# FZ-FILTER.net
KiCad netlist of a schematic drawn in EAGLE
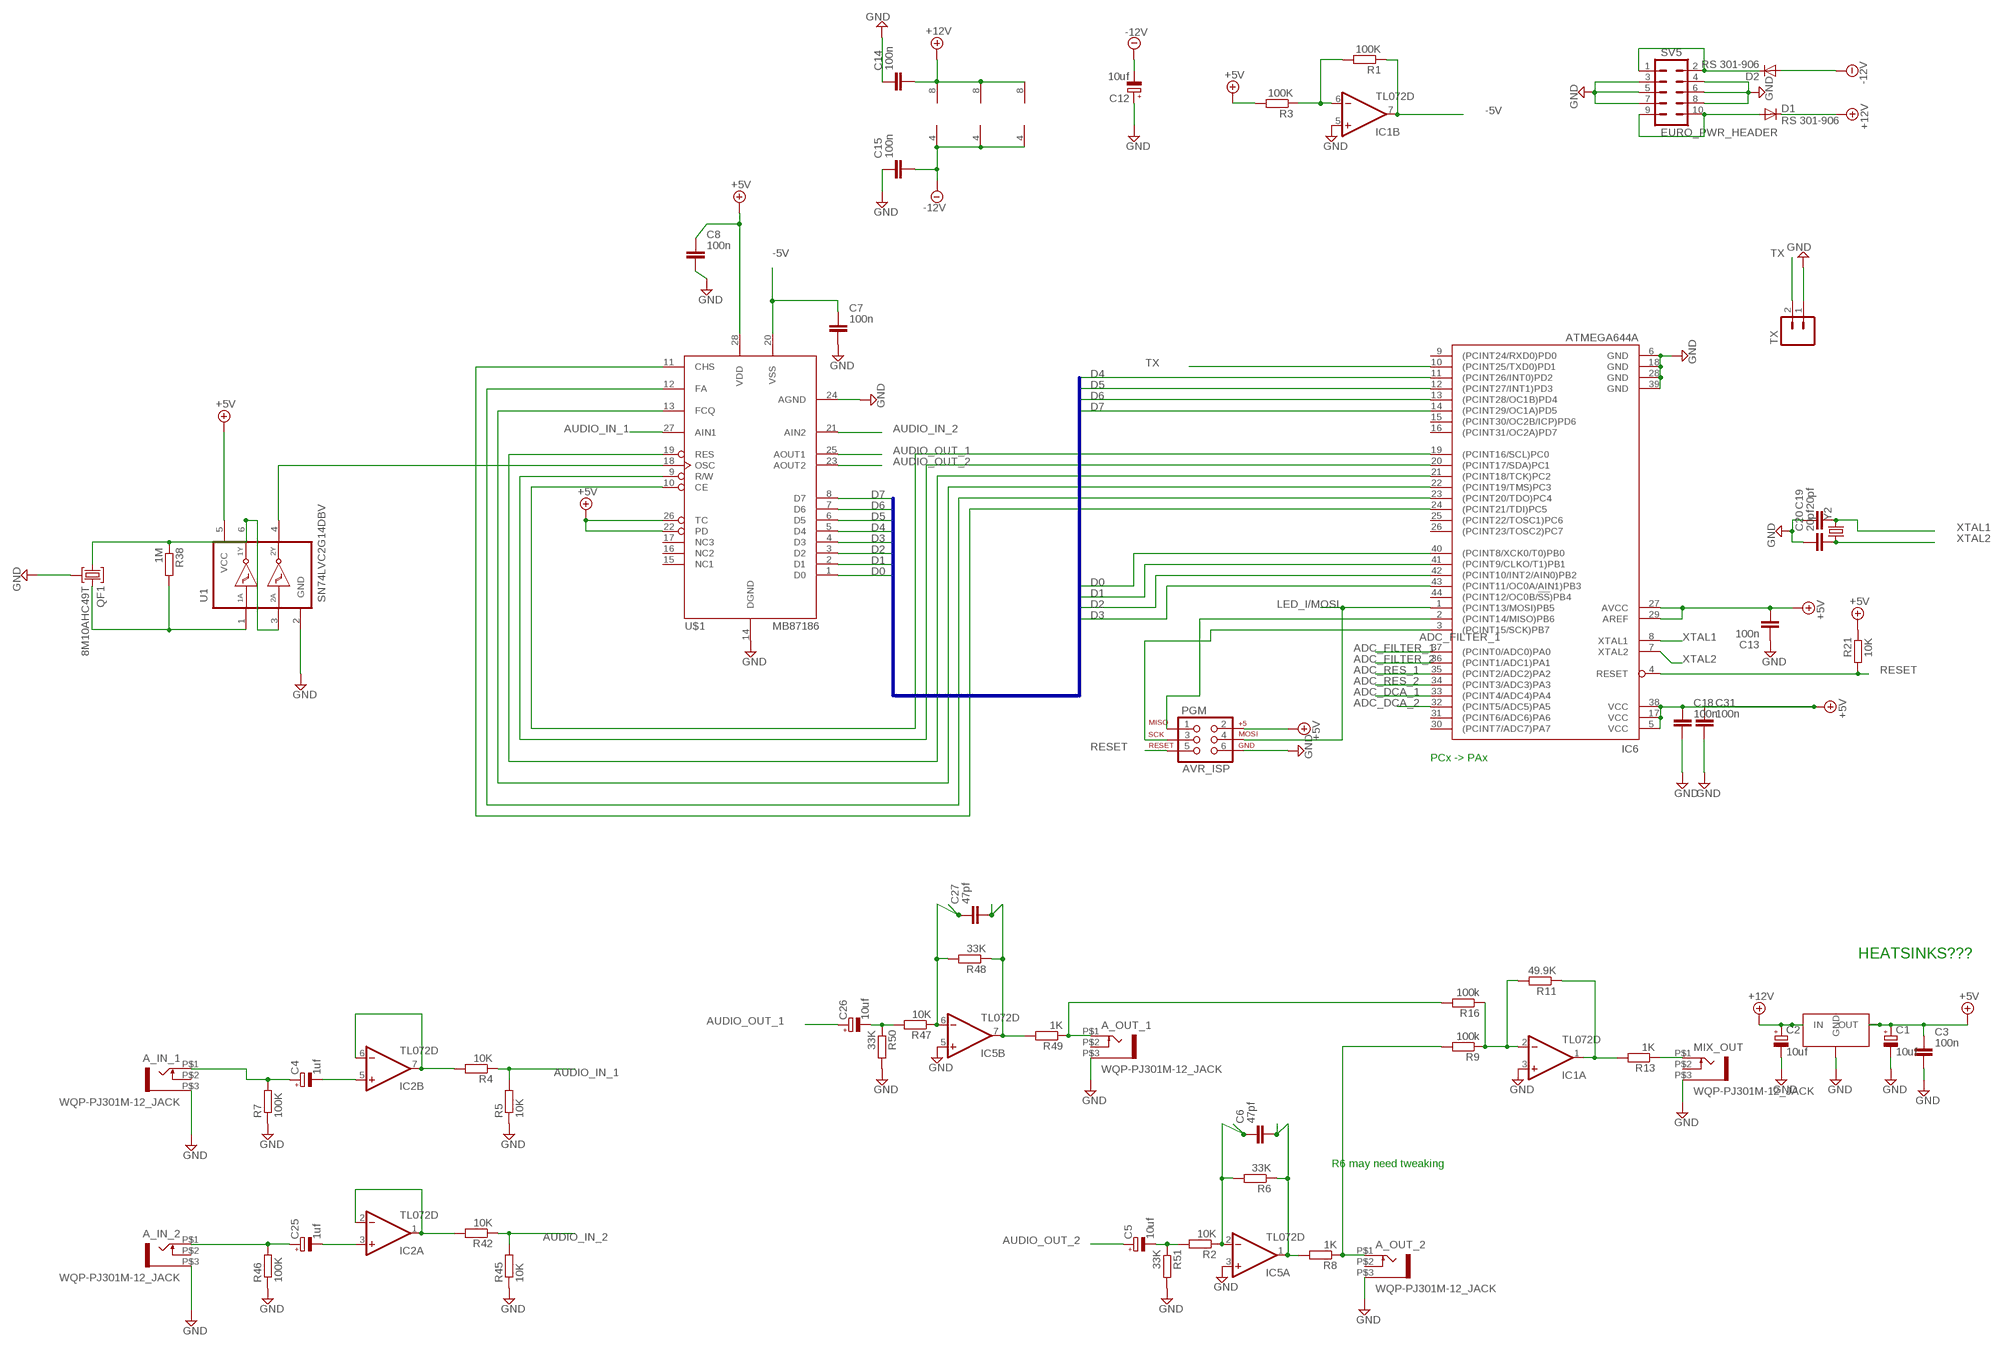
[diagram p0: schematic, sheet 1]
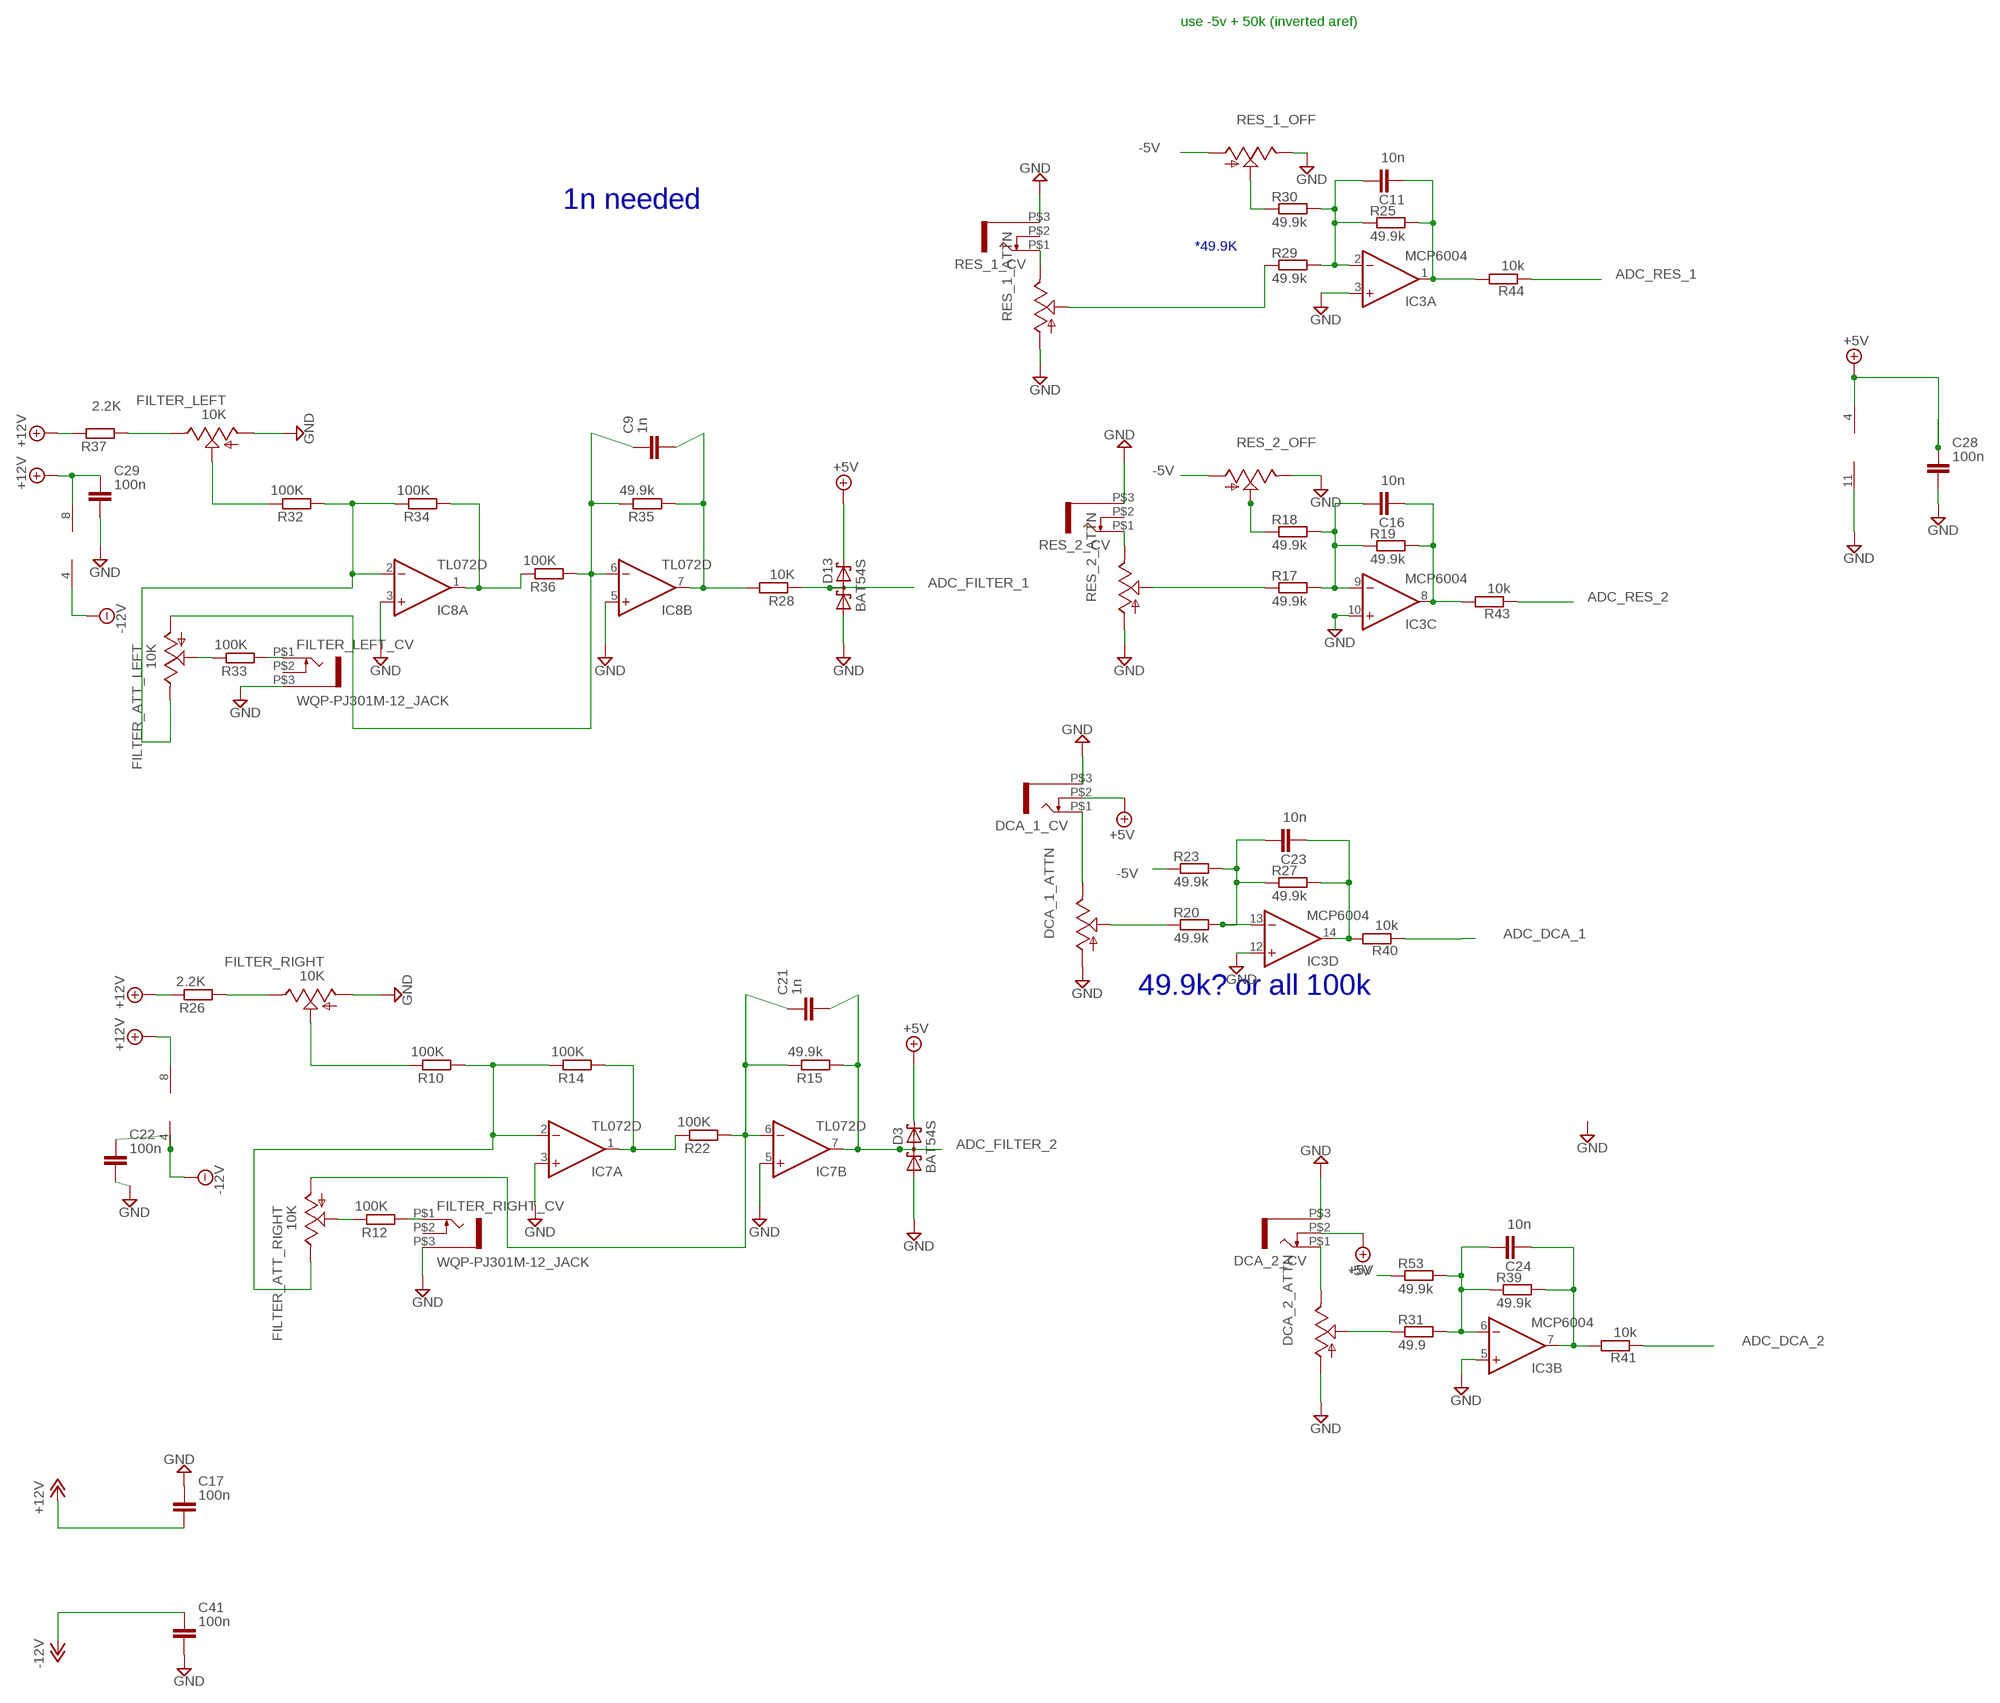
[diagram p1: schematic, sheet 2]

(export (version "E")
  (design (tool "Eeschema 10.0.6"))
  (components
    (comp (ref "C9")
      (value "1n")
      (footprint "eagle-import:C0603")
      (libsource (lib "eagle-import") (part "CAPACITOR0603"))
    )
    (comp (ref "C11")
      (value "10n")
      (footprint "eagle-import:C0603")
      (libsource (lib "eagle-import") (part "local_CAPACITOR0603"))
    )
    (comp (ref "C16")
      (value "10n")
      (footprint "eagle-import:C0603")
      (libsource (lib "eagle-import") (part "local_CAPACITOR0603"))
    )
    (comp (ref "C17")
      (value "100n")
      (footprint "eagle-import:C0603")
      (libsource (lib "eagle-import") (part "CAPACITOR0603"))
    )
    (comp (ref "C21")
      (value "1n")
      (footprint "eagle-import:C0603")
      (libsource (lib "eagle-import") (part "CAPACITOR0603"))
    )
    (comp (ref "C22")
      (value "100n")
      (footprint "eagle-import:C0603")
      (libsource (lib "eagle-import") (part "CAPACITOR0603"))
    )
    (comp (ref "C23")
      (value "10n")
      (footprint "eagle-import:C0603")
      (libsource (lib "eagle-import") (part "local_CAPACITOR0603"))
    )
    (comp (ref "C24")
      (value "10n")
      (footprint "eagle-import:C0603")
      (libsource (lib "eagle-import") (part "local_CAPACITOR0603"))
    )
    (comp (ref "C28")
      (value "100n")
      (footprint "eagle-import:C0603")
      (libsource (lib "eagle-import") (part "CAPACITOR0603"))
    )
    (comp (ref "C29")
      (value "100n")
      (footprint "eagle-import:C0603")
      (libsource (lib "eagle-import") (part "CAPACITOR0603"))
    )
    (comp (ref "C41")
      (value "100n")
      (footprint "eagle-import:C0603")
      (libsource (lib "eagle-import") (part "CAPACITOR0603"))
    )
    (comp (ref "D3")
      (value "BAT54S")
      (footprint "eagle-import:SOT23")
      (libsource (lib "eagle-import") (part "BAT54S"))
    )
    (comp (ref "D13")
      (value "BAT54S")
      (footprint "eagle-import:SOT23")
      (libsource (lib "eagle-import") (part "BAT54S"))
    )
    (comp (ref "DCA_1_ATTN")
      (value "ALPHA-9MMA")
      (footprint "eagle-import:EVUF")
      (libsource (lib "eagle-import") (part "ALPHA-9MMA"))
    )
    (comp (ref "DCA_1_CV")
      (value "WQP-PJ301M-12_JACK")
      (footprint "eagle-import:WQP-PJ301M-12_JACK")
      (libsource (lib "eagle-import") (part "WQP-PJ301M-12_JACK"))
    )
    (comp (ref "DCA_2_ATTN")
      (value "ALPHA-9MMA")
      (footprint "eagle-import:EVUF")
      (libsource (lib "eagle-import") (part "ALPHA-9MMA"))
    )
    (comp (ref "DCA_2_CV")
      (value "WQP-PJ301M-12_JACK")
      (footprint "eagle-import:WQP-PJ301M-12_JACK")
      (libsource (lib "eagle-import") (part "WQP-PJ301M-12_JACK"))
    )
    (comp (ref "FILTER_ATT_LEFT")
      (value "10K")
      (footprint "eagle-import:EVUF")
      (libsource (lib "eagle-import") (part "ALPHA-9MMA"))
    )
    (comp (ref "FILTER_ATT_RIGHT")
      (value "10K")
      (footprint "eagle-import:EVUF")
      (libsource (lib "eagle-import") (part "ALPHA-9MMA"))
    )
    (comp (ref "FILTER_LEFT")
      (value "10K")
      (footprint "eagle-import:EVUF")
      (libsource (lib "eagle-import") (part "ALPHA-9MMA"))
    )
    (comp (ref "FILTER_LEFT_CV")
      (value "WQP-PJ301M-12_JACK")
      (footprint "eagle-import:WQP-PJ301M-12_JACK")
      (libsource (lib "eagle-import") (part "WQP-PJ301M-12_JACK"))
    )
    (comp (ref "FILTER_RIGHT")
      (value "10K")
      (footprint "eagle-import:EVUF")
      (libsource (lib "eagle-import") (part "ALPHA-9MMA"))
    )
    (comp (ref "FILTER_RIGHT_CV")
      (value "WQP-PJ301M-12_JACK")
      (footprint "eagle-import:WQP-PJ301M-12_JACK")
      (libsource (lib "eagle-import") (part "WQP-PJ301M-12_JACK"))
    )
    (comp (ref "IC3")
      (value "MCP6004")
      (footprint "eagle-import:SO14")
      (libsource (lib "eagle-import") (part "TL074D"))
    )
    (comp (ref "IC7")
      (value "TL072D")
      (footprint "eagle-import:SO08")
      (libsource (lib "eagle-import") (part "TL072D"))
    )
    (comp (ref "IC8")
      (value "TL072D")
      (footprint "eagle-import:SO08")
      (libsource (lib "eagle-import") (part "TL072D"))
    )
    (comp (ref "R10")
      (value "100K")
      (footprint "eagle-import:R0603")
      (libsource (lib "eagle-import") (part "RESISTOR0603"))
    )
    (comp (ref "R12")
      (value "100K")
      (footprint "eagle-import:R0603")
      (libsource (lib "eagle-import") (part "RESISTOR0603"))
    )
    (comp (ref "R14")
      (value "100K")
      (footprint "eagle-import:R0603")
      (libsource (lib "eagle-import") (part "RESISTOR0603"))
    )
    (comp (ref "R15")
      (value "49.9k")
      (footprint "eagle-import:R0603")
      (libsource (lib "eagle-import") (part "RESISTOR0603"))
    )
    (comp (ref "R17")
      (value "49.9k")
      (footprint "eagle-import:R0603")
      (libsource (lib "eagle-import") (part "RESISTOR0603"))
    )
    (comp (ref "R18")
      (value "49.9k")
      (footprint "eagle-import:R0603")
      (libsource (lib "eagle-import") (part "RESISTOR0603"))
    )
    (comp (ref "R19")
      (value "49.9k")
      (footprint "eagle-import:R0603")
      (libsource (lib "eagle-import") (part "RESISTOR0603"))
    )
    (comp (ref "R20")
      (value "49.9k")
      (footprint "eagle-import:R0603")
      (libsource (lib "eagle-import") (part "RESISTOR0603"))
    )
    (comp (ref "R22")
      (value "100K")
      (footprint "eagle-import:R0603")
      (libsource (lib "eagle-import") (part "RESISTOR0603"))
    )
    (comp (ref "R23")
      (value "49.9k")
      (footprint "eagle-import:R0603")
      (libsource (lib "eagle-import") (part "RESISTOR0603"))
    )
    (comp (ref "R25")
      (value "49.9k")
      (footprint "eagle-import:R0603")
      (libsource (lib "eagle-import") (part "RESISTOR0603"))
    )
    (comp (ref "R26")
      (value "2.2K")
      (footprint "eagle-import:R0603")
      (libsource (lib "eagle-import") (part "RESISTOR0603"))
    )
    (comp (ref "R27")
      (value "49.9k")
      (footprint "eagle-import:R0603")
      (libsource (lib "eagle-import") (part "RESISTOR0603"))
    )
    (comp (ref "R28")
      (value "10K")
      (footprint "eagle-import:R0603")
      (libsource (lib "eagle-import") (part "RESISTOR0603"))
    )
    (comp (ref "R29")
      (value "49.9k")
      (footprint "eagle-import:R0603")
      (libsource (lib "eagle-import") (part "RESISTOR0603"))
    )
    (comp (ref "R30")
      (value "49.9k")
      (footprint "eagle-import:R0603")
      (libsource (lib "eagle-import") (part "RESISTOR0603"))
    )
    (comp (ref "R31")
      (value "49.9")
      (footprint "eagle-import:R0603")
      (libsource (lib "eagle-import") (part "RESISTOR0603"))
    )
    (comp (ref "R32")
      (value "100K")
      (footprint "eagle-import:R0603")
      (libsource (lib "eagle-import") (part "RESISTOR0603"))
    )
    (comp (ref "R33")
      (value "100K")
      (footprint "eagle-import:R0603")
      (libsource (lib "eagle-import") (part "RESISTOR0603"))
    )
    (comp (ref "R34")
      (value "100K")
      (footprint "eagle-import:R0603")
      (libsource (lib "eagle-import") (part "RESISTOR0603"))
    )
    (comp (ref "R35")
      (value "49.9k")
      (footprint "eagle-import:R0603")
      (libsource (lib "eagle-import") (part "RESISTOR0603"))
    )
    (comp (ref "R36")
      (value "100K")
      (footprint "eagle-import:R0603")
      (libsource (lib "eagle-import") (part "RESISTOR0603"))
    )
    (comp (ref "R37")
      (value "2.2K")
      (footprint "eagle-import:R0603")
      (libsource (lib "eagle-import") (part "RESISTOR0603"))
    )
    (comp (ref "R39")
      (value "49.9k")
      (footprint "eagle-import:R0603")
      (libsource (lib "eagle-import") (part "RESISTOR0603"))
    )
    (comp (ref "R40")
      (value "10k")
      (footprint "eagle-import:R0603")
      (libsource (lib "eagle-import") (part "RESISTOR0603"))
    )
    (comp (ref "R41")
      (value "10k")
      (footprint "eagle-import:R0603")
      (libsource (lib "eagle-import") (part "RESISTOR0603"))
    )
    (comp (ref "R43")
      (value "10k")
      (footprint "eagle-import:R0603")
      (libsource (lib "eagle-import") (part "RESISTOR0603"))
    )
    (comp (ref "R44")
      (value "10k")
      (footprint "eagle-import:R0603")
      (libsource (lib "eagle-import") (part "RESISTOR0603"))
    )
    (comp (ref "R53")
      (value "49.9k")
      (footprint "eagle-import:R0603")
      (libsource (lib "eagle-import") (part "RESISTOR0603"))
    )
    (comp (ref "RES_1_ATTN")
      (value "ALPHA-9MMA")
      (footprint "eagle-import:EVUF")
      (libsource (lib "eagle-import") (part "ALPHA-9MMA"))
    )
    (comp (ref "RES_1_CV")
      (value "WQP-PJ301M-12_JACK")
      (footprint "eagle-import:WQP-PJ301M-12_JACK")
      (libsource (lib "eagle-import") (part "WQP-PJ301M-12_JACK"))
    )
    (comp (ref "RES_1_OFF")
      (value "ALPHA-9MMA")
      (footprint "eagle-import:EVUF")
      (libsource (lib "eagle-import") (part "ALPHA-9MMA"))
    )
    (comp (ref "RES_2_ATTN")
      (value "ALPHA-9MMA")
      (footprint "eagle-import:EVUF")
      (libsource (lib "eagle-import") (part "ALPHA-9MMA"))
    )
    (comp (ref "RES_2_CV")
      (value "WQP-PJ301M-12_JACK")
      (footprint "eagle-import:WQP-PJ301M-12_JACK")
      (libsource (lib "eagle-import") (part "WQP-PJ301M-12_JACK"))
    )
    (comp (ref "RES_2_OFF")
      (value "ALPHA-9MMA")
      (footprint "eagle-import:EVUF")
      (libsource (lib "eagle-import") (part "ALPHA-9MMA"))
    )
    (comp (ref "A_IN_1")
      (value "WQP-PJ301M-12_JACK")
      (footprint "eagle-import:WQP-PJ301M-12_JACK")
      (libsource (lib "eagle-import") (part "WQP-PJ301M-12_JACK"))
    )
    (comp (ref "A_IN_2")
      (value "WQP-PJ301M-12_JACK")
      (footprint "eagle-import:WQP-PJ301M-12_JACK")
      (libsource (lib "eagle-import") (part "WQP-PJ301M-12_JACK"))
    )
    (comp (ref "A_OUT_1")
      (value "WQP-PJ301M-12_JACK")
      (footprint "eagle-import:WQP-PJ301M-12_JACK")
      (libsource (lib "eagle-import") (part "WQP-PJ301M-12_JACK"))
    )
    (comp (ref "A_OUT_2")
      (value "WQP-PJ301M-12_JACK")
      (footprint "eagle-import:WQP-PJ301M-12_JACK")
      (libsource (lib "eagle-import") (part "WQP-PJ301M-12_JACK"))
    )
    (comp (ref "C1")
      (value "10uf")
      (footprint "eagle-import:PANASONIC_B")
      (libsource (lib "eagle-import") (part "CPOL-EUB"))
    )
    (comp (ref "C2")
      (value "10uf")
      (footprint "eagle-import:PANASONIC_B")
      (libsource (lib "eagle-import") (part "CPOL-EUB"))
    )
    (comp (ref "C3")
      (value "100n")
      (footprint "eagle-import:C0603")
      (libsource (lib "eagle-import") (part "CAPACITOR0603"))
    )
    (comp (ref "C4")
      (value "1uf")
      (footprint "eagle-import:PANASONIC_B")
      (libsource (lib "eagle-import") (part "CPOL-EUB"))
    )
    (comp (ref "C5")
      (value "10uf")
      (footprint "eagle-import:PANASONIC_B")
      (libsource (lib "eagle-import") (part "CPOL-EUB"))
    )
    (comp (ref "C6")
      (value "47pf")
      (footprint "eagle-import:C0603")
      (libsource (lib "eagle-import") (part "CAPACITOR0603"))
    )
    (comp (ref "C7")
      (value "100n")
      (footprint "eagle-import:C0603")
      (libsource (lib "eagle-import") (part "CAPACITOR0603"))
    )
    (comp (ref "C8")
      (value "100n")
      (footprint "eagle-import:C0603")
      (libsource (lib "eagle-import") (part "CAPACITOR0603"))
    )
    (comp (ref "C12")
      (value "10uf")
      (footprint "eagle-import:PANASONIC_B")
      (libsource (lib "eagle-import") (part "CPOL-EUB"))
    )
    (comp (ref "C13")
      (value "100n")
      (footprint "eagle-import:C0603")
      (libsource (lib "eagle-import") (part "CAPACITOR0603"))
    )
    (comp (ref "C14")
      (value "100n")
      (footprint "eagle-import:C0603")
      (libsource (lib "eagle-import") (part "CAPACITOR0603"))
    )
    (comp (ref "C15")
      (value "100n")
      (footprint "eagle-import:C0603")
      (libsource (lib "eagle-import") (part "CAPACITOR0603"))
    )
    (comp (ref "C18")
      (value "100n")
      (footprint "eagle-import:C0603")
      (libsource (lib "eagle-import") (part "CAPACITOR0603"))
    )
    (comp (ref "C19")
      (value "20pf")
      (footprint "eagle-import:C0603")
      (libsource (lib "eagle-import") (part "CAPACITOR0603"))
    )
    (comp (ref "C20")
      (value "20pf")
      (footprint "eagle-import:C0603")
      (libsource (lib "eagle-import") (part "CAPACITOR0603"))
    )
    (comp (ref "C25")
      (value "1uf")
      (footprint "eagle-import:PANASONIC_B")
      (libsource (lib "eagle-import") (part "CPOL-EUB"))
    )
    (comp (ref "C26")
      (value "10uf")
      (footprint "eagle-import:PANASONIC_B")
      (libsource (lib "eagle-import") (part "CPOL-EUB"))
    )
    (comp (ref "C27")
      (value "47pf")
      (footprint "eagle-import:C0603")
      (libsource (lib "eagle-import") (part "CAPACITOR0603"))
    )
    (comp (ref "C31")
      (value "100n")
      (footprint "eagle-import:C0603")
      (libsource (lib "eagle-import") (part "CAPACITOR0603"))
    )
    (comp (ref "D1")
      (value "RS 301-906")
      (footprint "eagle-import:SMB-DIODE")
      (libsource (lib "eagle-import") (part "DIODESMB"))
    )
    (comp (ref "D2")
      (value "RS 301-906")
      (footprint "eagle-import:SMB-DIODE")
      (libsource (lib "eagle-import") (part "DIODESMB"))
    )
    (comp (ref "IC1")
      (value "TL072D")
      (footprint "eagle-import:SO08")
      (libsource (lib "eagle-import") (part "TL072D"))
    )
    (comp (ref "IC2")
      (value "TL072D")
      (footprint "eagle-import:SO08")
      (libsource (lib "eagle-import") (part "TL072D"))
    )
    (comp (ref "IC5")
      (value "TL072D")
      (footprint "eagle-import:SO08")
      (libsource (lib "eagle-import") (part "TL072D"))
    )
    (comp (ref "IC6")
      (value "ATMEGA644A")
      (footprint "eagle-import:TQFP44")
      (fields (field (name "MPN") "ATMEGA644PV-10AU"))
      (libsource (lib "eagle-import") (part "ATMEGA644A"))
    )
    (comp (ref "MIX_OUT")
      (value "WQP-PJ301M-12_JACK")
      (footprint "eagle-import:WQP-PJ301M-12_JACK")
      (libsource (lib "eagle-import") (part "WQP-PJ301M-12_JACK"))
    )
    (comp (ref "PGM")
      (value "AVR_ISP")
      (footprint "eagle-import:2X3")
      (libsource (lib "eagle-import") (part "AVR_SPI_PRG_6PTH"))
    )
    (comp (ref "QF1")
      (value "8M10AHC49T")
      (footprint "eagle-import:HC49U")
      (libsource (lib "eagle-import") (part "8M10AHC49T"))
    )
    (comp (ref "R1")
      (value "100K")
      (footprint "eagle-import:R0603")
      (libsource (lib "eagle-import") (part "RESISTOR0603"))
    )
    (comp (ref "R2")
      (value "10K")
      (footprint "eagle-import:R0603")
      (libsource (lib "eagle-import") (part "RESISTOR0603"))
    )
    (comp (ref "R3")
      (value "100K")
      (footprint "eagle-import:R0603")
      (libsource (lib "eagle-import") (part "RESISTOR0603"))
    )
    (comp (ref "R4")
      (value "10K")
      (footprint "eagle-import:R0603")
      (libsource (lib "eagle-import") (part "RESISTOR0603"))
    )
    (comp (ref "R5")
      (value "10K")
      (footprint "eagle-import:R0603")
      (libsource (lib "eagle-import") (part "RESISTOR0603"))
    )
    (comp (ref "R6")
      (value "33K")
      (footprint "eagle-import:R0603")
      (libsource (lib "eagle-import") (part "RESISTOR0603"))
    )
    (comp (ref "R7")
      (value "100K")
      (footprint "eagle-import:R0603")
      (libsource (lib "eagle-import") (part "RESISTOR0603"))
    )
    (comp (ref "R8")
      (value "1K")
      (footprint "eagle-import:R0603")
      (libsource (lib "eagle-import") (part "RESISTOR0603"))
    )
    (comp (ref "R9")
      (value "100k")
      (footprint "eagle-import:R0603")
      (libsource (lib "eagle-import") (part "RESISTOR0603"))
    )
    (comp (ref "R11")
      (value "49.9K")
      (footprint "eagle-import:R0603")
      (libsource (lib "eagle-import") (part "RESISTOR0603"))
    )
    (comp (ref "R13")
      (value "1K")
      (footprint "eagle-import:R0603")
      (libsource (lib "eagle-import") (part "RESISTOR0603"))
    )
    (comp (ref "R16")
      (value "100k")
      (footprint "eagle-import:R0603")
      (libsource (lib "eagle-import") (part "RESISTOR0603"))
    )
    (comp (ref "R21")
      (value "10K")
      (footprint "eagle-import:R0603")
      (libsource (lib "eagle-import") (part "RESISTOR0603"))
    )
    (comp (ref "R38")
      (value "1M")
      (footprint "eagle-import:R0603")
      (libsource (lib "eagle-import") (part "RESISTOR0603"))
    )
    (comp (ref "R42")
      (value "10K")
      (footprint "eagle-import:R0603")
      (libsource (lib "eagle-import") (part "RESISTOR0603"))
    )
    (comp (ref "R45")
      (value "10K")
      (footprint "eagle-import:R0603")
      (libsource (lib "eagle-import") (part "RESISTOR0603"))
    )
    (comp (ref "R46")
      (value "100K")
      (footprint "eagle-import:R0603")
      (libsource (lib "eagle-import") (part "RESISTOR0603"))
    )
    (comp (ref "R47")
      (value "10K")
      (footprint "eagle-import:R0603")
      (libsource (lib "eagle-import") (part "RESISTOR0603"))
    )
    (comp (ref "R48")
      (value "33K")
      (footprint "eagle-import:R0603")
      (libsource (lib "eagle-import") (part "RESISTOR0603"))
    )
    (comp (ref "R49")
      (value "1K")
      (footprint "eagle-import:R0603")
      (libsource (lib "eagle-import") (part "RESISTOR0603"))
    )
    (comp (ref "R50")
      (value "33K")
      (footprint "eagle-import:R0603")
      (libsource (lib "eagle-import") (part "RESISTOR0603"))
    )
    (comp (ref "R51")
      (value "33K")
      (footprint "eagle-import:R0603")
      (libsource (lib "eagle-import") (part "RESISTOR0603"))
    )
    (comp (ref "SV5")
      (value "EURO_PWR_HEADER")
      (footprint "eagle-import:EURO_PWR_HEADER")
      (libsource (lib "eagle-import") (part "EURO_PWR_HEADER"))
    )
    (comp (ref "TX")
      (value "M02PTH")
      (footprint "eagle-import:1X02")
      (libsource (lib "eagle-import") (part "M02PTH"))
    )
    (comp (ref "U$1")
      (value "MB87186")
      (footprint "eagle-import:DIP28")
      (libsource (lib "eagle-import") (part "MB87186"))
    )
    (comp (ref "U1")
      (value "SN74LVC2G14DBV")
      (footprint "eagle-import:SOT23-6")
      (libsource (lib "eagle-import") (part "SN74LVC2G14DBV"))
    )
    (comp (ref "U3")
      (value "7805")
      (footprint "eagle-import:VREG-7805-DPAK2")
      (libsource (lib "eagle-import") (part "VREG-7805-DPAK2"))
    )
    (comp (ref "Y2")
      (value "CRYSTALSMD")
      (footprint "eagle-import:HC49UP")
      (libsource (lib "eagle-import") (part "CRYSTALSMD"))
    )
  )
  (nets
    (net (code "1") (name "+5V") (class "Default")
      (node (ref "C1") (pin "+") (pinfunction "+_+") (pintype "passive"))
      (node (ref "C13") (pin "2") (pinfunction "2_2") (pintype "passive"))
      (node (ref "C18") (pin "1") (pinfunction "1_1") (pintype "passive"))
      (node (ref "C28") (pin "1") (pinfunction "1_1") (pintype "passive"))
      (node (ref "C3") (pin "1") (pinfunction "1_1") (pintype "passive"))
      (node (ref "C31") (pin "1") (pinfunction "1_1") (pintype "passive"))
      (node (ref "C8") (pin "1") (pinfunction "1_1") (pintype "passive"))
      (node (ref "D13") (pin "2") (pinfunction "C2_2") (pintype "passive"))
      (node (ref "D3") (pin "2") (pinfunction "C2_2") (pintype "passive"))
      (node (ref "DCA_1_CV") (pin "P$2") (pinfunction "3_P$2") (pintype "passive"))
      (node (ref "DCA_2_CV") (pin "P$2") (pinfunction "3_P$2") (pintype "passive"))
      (node (ref "IC3") (pin "4") (pinfunction "V+_4") (pintype "power_in"))
      (node (ref "IC6") (pin "17") (pinfunction "VCC_17") (pintype "power_in"))
      (node (ref "IC6") (pin "27") (pinfunction "AVCC_27") (pintype "power_in"))
      (node (ref "IC6") (pin "29") (pinfunction "AREF_29") (pintype "passive"))
      (node (ref "IC6") (pin "38") (pinfunction "VCC_38") (pintype "power_in"))
      (node (ref "IC6") (pin "5") (pinfunction "VCC_5") (pintype "power_in"))
      (node (ref "PGM") (pin "2") (pinfunction "2_2") (pintype "passive"))
      (node (ref "R21") (pin "2") (pinfunction "2_2") (pintype "passive"))
      (node (ref "R3") (pin "2") (pinfunction "2_2") (pintype "passive"))
      (node (ref "U$1") (pin "22") (pinfunction "PD_22") (pintype "input"))
      (node (ref "U$1") (pin "26") (pinfunction "TC_26") (pintype "input"))
      (node (ref "U$1") (pin "28") (pinfunction "VDD_28") (pintype "power_in"))
      (node (ref "U1") (pin "5") (pinfunction "VCC_5") (pintype "power_in"))
      (node (ref "U3") (pin "VOUT") (pinfunction "OUT_VOUT") (pintype "bidirectional"))
    )
    (net (code "2") (name "+12V") (class "Default")
      (node (ref "C14") (pin "2") (pinfunction "2_2") (pintype "passive"))
      (node (ref "C17") (pin "2") (pinfunction "2_2") (pintype "passive"))
      (node (ref "C2") (pin "+") (pinfunction "+_+") (pintype "passive"))
      (node (ref "C29") (pin "1") (pinfunction "1_1") (pintype "passive"))
      (node (ref "D1") (pin "C") (pinfunction "C_C") (pintype "passive"))
      (node (ref "IC1") (pin "8") (pinfunction "V+_8") (pintype "power_in"))
      (node (ref "IC2") (pin "8") (pinfunction "V+_8") (pintype "power_in"))
      (node (ref "IC5") (pin "8") (pinfunction "V+_8") (pintype "power_in"))
      (node (ref "IC7") (pin "8") (pinfunction "V+_8") (pintype "power_in"))
      (node (ref "IC8") (pin "8") (pinfunction "V+_8") (pintype "power_in"))
      (node (ref "R26") (pin "2") (pinfunction "2_2") (pintype "passive"))
      (node (ref "R37") (pin "2") (pinfunction "2_2") (pintype "passive"))
      (node (ref "U3") (pin "VIN") (pinfunction "IN_VIN") (pintype "bidirectional"))
    )
    (net (code "3") (name "-5V") (class "Default")
      (node (ref "C7") (pin "1") (pinfunction "1_1") (pintype "passive"))
      (node (ref "IC1") (pin "7") (pinfunction "OUT_7") (pintype "output"))
      (node (ref "R1") (pin "1") (pinfunction "1_1") (pintype "passive"))
      (node (ref "R23") (pin "1") (pinfunction "1_1") (pintype "passive"))
      (node (ref "R53") (pin "1") (pinfunction "1_1") (pintype "passive"))
      (node (ref "RES_1_OFF") (pin "1") (pinfunction "A_1") (pintype "passive"))
      (node (ref "RES_2_OFF") (pin "1") (pinfunction "A_1") (pintype "passive"))
      (node (ref "U$1") (pin "20") (pinfunction "VSS_20") (pintype "power_in"))
    )
    (net (code "4") (name "-12V") (class "Default")
      (node (ref "C12") (pin "-") (pinfunction "-_-") (pintype "passive"))
      (node (ref "C15") (pin "2") (pinfunction "2_2") (pintype "passive"))
      (node (ref "C22") (pin "1") (pinfunction "1_1") (pintype "passive"))
      (node (ref "C41") (pin "1") (pinfunction "1_1") (pintype "passive"))
      (node (ref "D2") (pin "A") (pinfunction "A_A") (pintype "passive"))
      (node (ref "IC1") (pin "4") (pinfunction "V-_4") (pintype "power_in"))
      (node (ref "IC2") (pin "4") (pinfunction "V-_4") (pintype "power_in"))
      (node (ref "IC5") (pin "4") (pinfunction "V-_4") (pintype "power_in"))
      (node (ref "IC7") (pin "4") (pinfunction "V-_4") (pintype "power_in"))
      (node (ref "IC8") (pin "4") (pinfunction "V-_4") (pintype "power_in"))
    )
    (net (code "5") (name "ADC_DCA_1") (class "Default")
      (node (ref "IC6") (pin "33") (pinfunction "(PCINT4/ADC4)PA4_33") (pintype "bidirectional"))
      (node (ref "R40") (pin "1") (pinfunction "1_1") (pintype "passive"))
    )
    (net (code "6") (name "ADC_DCA_2") (class "Default")
      (node (ref "IC6") (pin "32") (pinfunction "(PCINT5/ADC5)PA5_32") (pintype "bidirectional"))
      (node (ref "R41") (pin "1") (pinfunction "1_1") (pintype "passive"))
    )
    (net (code "7") (name "ADC_FILTER_1") (class "Default")
      (node (ref "D13") (pin "3") (pinfunction "C1A2_3") (pintype "passive"))
      (node (ref "IC6") (pin "37") (pinfunction "(PCINT0/ADC0)PA0_37") (pintype "bidirectional"))
      (node (ref "R28") (pin "1") (pinfunction "1_1") (pintype "passive"))
    )
    (net (code "8") (name "ADC_FILTER_2") (class "Default")
      (node (ref "C21") (pin "2") (pinfunction "2_2") (pintype "passive"))
      (node (ref "D3") (pin "3") (pinfunction "C1A2_3") (pintype "passive"))
      (node (ref "IC6") (pin "36") (pinfunction "(PCINT1/ADC1)PA1_36") (pintype "bidirectional"))
      (node (ref "IC7") (pin "7") (pinfunction "OUT_7") (pintype "output"))
      (node (ref "R15") (pin "1") (pinfunction "1_1") (pintype "passive"))
    )
    (net (code "9") (name "ADC_RES_1") (class "Default")
      (node (ref "IC6") (pin "35") (pinfunction "(PCINT2/ADC2)PA2_35") (pintype "bidirectional"))
      (node (ref "R44") (pin "1") (pinfunction "1_1") (pintype "passive"))
    )
    (net (code "10") (name "ADC_RES_2") (class "Default")
      (node (ref "IC6") (pin "34") (pinfunction "(PCINT3/ADC3)PA3_34") (pintype "bidirectional"))
      (node (ref "R43") (pin "1") (pinfunction "1_1") (pintype "passive"))
    )
    (net (code "11") (name "AUDIO_IN_1") (class "Default")
      (node (ref "R4") (pin "1") (pinfunction "1_1") (pintype "passive"))
      (node (ref "R5") (pin "2") (pinfunction "2_2") (pintype "passive"))
      (node (ref "U$1") (pin "27") (pinfunction "AIN1_27") (pintype "bidirectional"))
    )
    (net (code "12") (name "AUDIO_IN_2") (class "Default")
      (node (ref "R42") (pin "1") (pinfunction "1_1") (pintype "passive"))
      (node (ref "R45") (pin "2") (pinfunction "2_2") (pintype "passive"))
      (node (ref "U$1") (pin "21") (pinfunction "AIN2_21") (pintype "input"))
    )
    (net (code "13") (name "AUDIO_OUT_1") (class "Default")
      (node (ref "C26") (pin "+") (pinfunction "+_+") (pintype "passive"))
      (node (ref "U$1") (pin "25") (pinfunction "AOUT1_25") (pintype "tri_state"))
    )
    (net (code "14") (name "AUDIO_OUT_2") (class "Default")
      (node (ref "C5") (pin "+") (pinfunction "+_+") (pintype "passive"))
      (node (ref "U$1") (pin "23") (pinfunction "AOUT2_23") (pintype "tri_state"))
    )
    (net (code "15") (name "D0") (class "Default")
      (node (ref "IC6") (pin "40") (pinfunction "(PCINT8/XCK0/T0)PB0_40") (pintype "bidirectional"))
      (node (ref "U$1") (pin "1") (pinfunction "D0_1") (pintype "bidirectional"))
    )
    (net (code "16") (name "D1") (class "Default")
      (node (ref "IC6") (pin "41") (pinfunction "(PCINT9/CLKO/T1)PB1_41") (pintype "bidirectional"))
      (node (ref "U$1") (pin "2") (pinfunction "D1_2") (pintype "bidirectional"))
    )
    (net (code "17") (name "D2") (class "Default")
      (node (ref "IC6") (pin "42") (pinfunction "(PCINT10/INT2/AIN0)PB2_42") (pintype "bidirectional"))
      (node (ref "U$1") (pin "3") (pinfunction "D2_3") (pintype "bidirectional"))
    )
    (net (code "18") (name "D3") (class "Default")
      (node (ref "IC6") (pin "43") (pinfunction "(PCINT11/OC0A/AIN1)PB3_43") (pintype "bidirectional"))
      (node (ref "U$1") (pin "4") (pinfunction "D3_4") (pintype "bidirectional"))
    )
    (net (code "19") (name "D4") (class "Default")
      (node (ref "IC6") (pin "11") (pinfunction "(PCINT26/INT0)PD2_11") (pintype "bidirectional"))
      (node (ref "U$1") (pin "5") (pinfunction "D4_5") (pintype "bidirectional"))
    )
    (net (code "20") (name "D5") (class "Default")
      (node (ref "IC6") (pin "12") (pinfunction "(PCINT27/INT1)PD3_12") (pintype "bidirectional"))
      (node (ref "U$1") (pin "6") (pinfunction "D5_6") (pintype "bidirectional"))
    )
    (net (code "21") (name "D6") (class "Default")
      (node (ref "IC6") (pin "13") (pinfunction "(PCINT28/OC1B)PD4_13") (pintype "bidirectional"))
      (node (ref "U$1") (pin "7") (pinfunction "D6_7") (pintype "bidirectional"))
    )
    (net (code "22") (name "D7") (class "Default")
      (node (ref "IC6") (pin "14") (pinfunction "(PCINT29/OC1A)PD5_14") (pintype "bidirectional"))
      (node (ref "U$1") (pin "8") (pinfunction "D7_8") (pintype "bidirectional"))
    )
    (net (code "23") (name "GND") (class "Default")
      (node (ref "A_IN_1") (pin "P$3") (pinfunction "1_P$3") (pintype "passive"))
      (node (ref "A_IN_2") (pin "P$3") (pinfunction "1_P$3") (pintype "passive"))
      (node (ref "A_OUT_1") (pin "P$3") (pinfunction "1_P$3") (pintype "passive"))
      (node (ref "A_OUT_2") (pin "P$3") (pinfunction "1_P$3") (pintype "passive"))
      (node (ref "C1") (pin "-") (pinfunction "-_-") (pintype "passive"))
      (node (ref "C12") (pin "+") (pinfunction "+_+") (pintype "passive"))
      (node (ref "C13") (pin "1") (pinfunction "1_1") (pintype "passive"))
      (node (ref "C14") (pin "1") (pinfunction "1_1") (pintype "passive"))
      (node (ref "C15") (pin "1") (pinfunction "1_1") (pintype "passive"))
      (node (ref "C17") (pin "1") (pinfunction "1_1") (pintype "passive"))
      (node (ref "C18") (pin "2") (pinfunction "2_2") (pintype "passive"))
      (node (ref "C19") (pin "1") (pinfunction "1_1") (pintype "passive"))
      (node (ref "C2") (pin "-") (pinfunction "-_-") (pintype "passive"))
      (node (ref "C20") (pin "1") (pinfunction "1_1") (pintype "passive"))
      (node (ref "C22") (pin "2") (pinfunction "2_2") (pintype "passive"))
      (node (ref "C28") (pin "2") (pinfunction "2_2") (pintype "passive"))
      (node (ref "C29") (pin "2") (pinfunction "2_2") (pintype "passive"))
      (node (ref "C3") (pin "2") (pinfunction "2_2") (pintype "passive"))
      (node (ref "C31") (pin "2") (pinfunction "2_2") (pintype "passive"))
      (node (ref "C41") (pin "2") (pinfunction "2_2") (pintype "passive"))
      (node (ref "C7") (pin "2") (pinfunction "2_2") (pintype "passive"))
      (node (ref "C8") (pin "2") (pinfunction "2_2") (pintype "passive"))
      (node (ref "D13") (pin "1") (pinfunction "A1_1") (pintype "passive"))
      (node (ref "D3") (pin "1") (pinfunction "A1_1") (pintype "passive"))
      (node (ref "DCA_1_ATTN") (pin "1") (pinfunction "A_1") (pintype "passive"))
      (node (ref "DCA_1_CV") (pin "P$3") (pinfunction "1_P$3") (pintype "passive"))
      (node (ref "DCA_2_ATTN") (pin "1") (pinfunction "A_1") (pintype "passive"))
      (node (ref "DCA_2_CV") (pin "P$3") (pinfunction "1_P$3") (pintype "passive"))
      (node (ref "FILTER_LEFT") (pin "1") (pinfunction "A_1") (pintype "passive"))
      (node (ref "FILTER_LEFT_CV") (pin "P$3") (pinfunction "1_P$3") (pintype "passive"))
      (node (ref "FILTER_RIGHT") (pin "1") (pinfunction "A_1") (pintype "passive"))
      (node (ref "FILTER_RIGHT_CV") (pin "P$3") (pinfunction "1_P$3") (pintype "passive"))
      (node (ref "IC1") (pin "3") (pinfunction "+IN_3") (pintype "input"))
      (node (ref "IC1") (pin "5") (pinfunction "+IN_5") (pintype "input"))
      (node (ref "IC3") (pin "10") (pinfunction "+IN_10") (pintype "input"))
      (node (ref "IC3") (pin "11") (pinfunction "V-_11") (pintype "power_in"))
      (node (ref "IC3") (pin "12") (pinfunction "+IN_12") (pintype "input"))
      (node (ref "IC3") (pin "3") (pinfunction "+IN_3") (pintype "input"))
      (node (ref "IC3") (pin "5") (pinfunction "+IN_5") (pintype "input"))
      (node (ref "IC5") (pin "3") (pinfunction "+IN_3") (pintype "input"))
      (node (ref "IC5") (pin "5") (pinfunction "+IN_5") (pintype "input"))
      (node (ref "IC6") (pin "18") (pinfunction "GND_18") (pintype "power_in"))
      (node (ref "IC6") (pin "28") (pinfunction "GND_28") (pintype "power_in"))
      (node (ref "IC6") (pin "39") (pinfunction "GND_39") (pintype "power_in"))
      (node (ref "IC6") (pin "6") (pinfunction "GND_6") (pintype "power_in"))
      (node (ref "IC7") (pin "3") (pinfunction "+IN_3") (pintype "input"))
      (node (ref "IC7") (pin "5") (pinfunction "+IN_5") (pintype "input"))
      (node (ref "IC8") (pin "3") (pinfunction "+IN_3") (pintype "input"))
      (node (ref "IC8") (pin "5") (pinfunction "+IN_5") (pintype "input"))
      (node (ref "MIX_OUT") (pin "P$3") (pinfunction "1_P$3") (pintype "passive"))
      (node (ref "PGM") (pin "6") (pinfunction "6_6") (pintype "passive"))
      (node (ref "QF1") (pin "2") (pinfunction "2_2") (pintype "passive"))
      (node (ref "R45") (pin "1") (pinfunction "1_1") (pintype "passive"))
      (node (ref "R46") (pin "1") (pinfunction "1_1") (pintype "passive"))
      (node (ref "R5") (pin "1") (pinfunction "1_1") (pintype "passive"))
      (node (ref "R50") (pin "2") (pinfunction "2_2") (pintype "passive"))
      (node (ref "R51") (pin "2") (pinfunction "2_2") (pintype "passive"))
      (node (ref "R7") (pin "1") (pinfunction "1_1") (pintype "passive"))
      (node (ref "RES_1_ATTN") (pin "1") (pinfunction "A_1") (pintype "passive"))
      (node (ref "RES_1_CV") (pin "P$3") (pinfunction "1_P$3") (pintype "passive"))
      (node (ref "RES_1_OFF") (pin "3") (pinfunction "E_3") (pintype "passive"))
      (node (ref "RES_2_ATTN") (pin "1") (pinfunction "A_1") (pintype "passive"))
      (node (ref "RES_2_CV") (pin "P$3") (pinfunction "1_P$3") (pintype "passive"))
      (node (ref "RES_2_OFF") (pin "3") (pinfunction "E_3") (pintype "passive"))
      (node (ref "SV5") (pin "3") (pinfunction "3_3") (pintype "passive"))
      (node (ref "SV5") (pin "4") (pinfunction "4_4") (pintype "passive"))
      (node (ref "SV5") (pin "5") (pinfunction "5_5") (pintype "passive"))
      (node (ref "SV5") (pin "6") (pinfunction "6_6") (pintype "passive"))
      (node (ref "SV5") (pin "7") (pinfunction "7_7") (pintype "passive"))
      (node (ref "SV5") (pin "8") (pinfunction "8_8") (pintype "passive"))
      (node (ref "TX") (pin "1") (pinfunction "1_1") (pintype "passive"))
      (node (ref "U$1") (pin "14") (pinfunction "DGND_14") (pintype "power_in"))
      (node (ref "U$1") (pin "24") (pinfunction "AGND_24") (pintype "power_in"))
      (node (ref "U1") (pin "2") (pinfunction "GND_2") (pintype "power_in"))
      (node (ref "U3") (pin "GND") (pinfunction "GND_GND") (pintype "bidirectional"))
    )
    (net (code "24") (name "LED_I{slash}MOSI") (class "Default")
      (node (ref "IC6") (pin "1") (pinfunction "(PCINT13/MOSI)PB5_1") (pintype "bidirectional"))
      (node (ref "PGM") (pin "4") (pinfunction "4_4") (pintype "passive"))
    )
    (net (code "25") (name "Net-(A_IN_1-2)") (class "Default")
      (node (ref "A_IN_1") (pin "P$1") (pinfunction "2_P$1") (pintype "passive"))
      (node (ref "C4") (pin "+") (pinfunction "+_+") (pintype "passive"))
      (node (ref "R7") (pin "2") (pinfunction "2_2") (pintype "passive"))
    )
    (net (code "26") (name "Net-(A_IN_2-2)") (class "Default")
      (node (ref "A_IN_2") (pin "P$1") (pinfunction "2_P$1") (pintype "passive"))
      (node (ref "C25") (pin "+") (pinfunction "+_+") (pintype "passive"))
      (node (ref "R46") (pin "2") (pinfunction "2_2") (pintype "passive"))
    )
    (net (code "27") (name "Net-(A_OUT_1-2)") (class "Default")
      (node (ref "A_OUT_1") (pin "P$1") (pinfunction "2_P$1") (pintype "passive"))
      (node (ref "R16") (pin "2") (pinfunction "2_2") (pintype "passive"))
      (node (ref "R49") (pin "1") (pinfunction "1_1") (pintype "passive"))
    )
    (net (code "28") (name "Net-(A_OUT_2-2)") (class "Default")
      (node (ref "A_OUT_2") (pin "P$1") (pinfunction "2_P$1") (pintype "passive"))
      (node (ref "R8") (pin "1") (pinfunction "1_1") (pintype "passive"))
      (node (ref "R9") (pin "2") (pinfunction "2_2") (pintype "passive"))
    )
    (net (code "29") (name "Net-(C5-Pad-)") (class "Default")
      (node (ref "C5") (pin "-") (pinfunction "-_-") (pintype "passive"))
      (node (ref "R2") (pin "2") (pinfunction "2_2") (pintype "passive"))
      (node (ref "R51") (pin "1") (pinfunction "1_1") (pintype "passive"))
    )
    (net (code "30") (name "Net-(C26-Pad-)") (class "Default")
      (node (ref "C26") (pin "-") (pinfunction "-_-") (pintype "passive"))
      (node (ref "R47") (pin "2") (pinfunction "2_2") (pintype "passive"))
      (node (ref "R50") (pin "1") (pinfunction "1_1") (pintype "passive"))
    )
    (net (code "31") (name "Net-(D1-PadA)") (class "Default")
      (node (ref "D1") (pin "A") (pinfunction "A_A") (pintype "passive"))
      (node (ref "SV5") (pin "10") (pinfunction "10_10") (pintype "passive"))
      (node (ref "SV5") (pin "9") (pinfunction "9_9") (pintype "passive"))
    )
    (net (code "32") (name "Net-(D2-PadC)") (class "Default")
      (node (ref "D2") (pin "C") (pinfunction "C_C") (pintype "passive"))
      (node (ref "SV5") (pin "1") (pinfunction "1_1") (pintype "passive"))
      (node (ref "SV5") (pin "2") (pinfunction "2_2") (pintype "passive"))
    )
    (net (code "33") (name "Net-(DCA_1_ATTN-E)") (class "Default")
      (node (ref "DCA_1_ATTN") (pin "3") (pinfunction "E_3") (pintype "passive"))
      (node (ref "DCA_1_CV") (pin "P$1") (pinfunction "2_P$1") (pintype "passive"))
    )
    (net (code "34") (name "Net-(DCA_1_ATTN-S)") (class "Default")
      (node (ref "DCA_1_ATTN") (pin "2") (pinfunction "S_2") (pintype "passive"))
      (node (ref "R20") (pin "1") (pinfunction "1_1") (pintype "passive"))
    )
    (net (code "35") (name "Net-(DCA_2_ATTN-E)") (class "Default")
      (node (ref "DCA_2_ATTN") (pin "3") (pinfunction "E_3") (pintype "passive"))
      (node (ref "DCA_2_CV") (pin "P$1") (pinfunction "2_P$1") (pintype "passive"))
    )
    (net (code "36") (name "Net-(DCA_2_ATTN-S)") (class "Default")
      (node (ref "DCA_2_ATTN") (pin "2") (pinfunction "S_2") (pintype "passive"))
      (node (ref "R31") (pin "1") (pinfunction "1_1") (pintype "passive"))
    )
    (net (code "37") (name "Net-(FILTER_ATT_LEFT-A)") (class "Default")
      (node (ref "C9") (pin "1") (pinfunction "1_1") (pintype "passive"))
      (node (ref "FILTER_ATT_LEFT") (pin "1") (pinfunction "A_1") (pintype "passive"))
      (node (ref "IC8") (pin "6") (pinfunction "-IN_6") (pintype "input"))
      (node (ref "R35") (pin "2") (pinfunction "2_2") (pintype "passive"))
      (node (ref "R36") (pin "1") (pinfunction "1_1") (pintype "passive"))
    )
    (net (code "38") (name "Net-(FILTER_ATT_LEFT-E)") (class "Default")
      (node (ref "FILTER_ATT_LEFT") (pin "3") (pinfunction "E_3") (pintype "passive"))
      (node (ref "IC8") (pin "2") (pinfunction "-IN_2") (pintype "input"))
      (node (ref "R32") (pin "1") (pinfunction "1_1") (pintype "passive"))
      (node (ref "R34") (pin "2") (pinfunction "2_2") (pintype "passive"))
    )
    (net (code "39") (name "Net-(FILTER_ATT_LEFT-S)") (class "Default")
      (node (ref "FILTER_ATT_LEFT") (pin "2") (pinfunction "S_2") (pintype "passive"))
      (node (ref "R33") (pin "2") (pinfunction "2_2") (pintype "passive"))
    )
    (net (code "40") (name "Net-(FILTER_ATT_RIGHT-A)") (class "Default")
      (node (ref "C21") (pin "1") (pinfunction "1_1") (pintype "passive"))
      (node (ref "FILTER_ATT_RIGHT") (pin "1") (pinfunction "A_1") (pintype "passive"))
      (node (ref "IC7") (pin "6") (pinfunction "-IN_6") (pintype "input"))
      (node (ref "R15") (pin "2") (pinfunction "2_2") (pintype "passive"))
      (node (ref "R22") (pin "1") (pinfunction "1_1") (pintype "passive"))
    )
    (net (code "41") (name "Net-(FILTER_ATT_RIGHT-E)") (class "Default")
      (node (ref "FILTER_ATT_RIGHT") (pin "3") (pinfunction "E_3") (pintype "passive"))
      (node (ref "IC7") (pin "2") (pinfunction "-IN_2") (pintype "input"))
      (node (ref "R10") (pin "1") (pinfunction "1_1") (pintype "passive"))
      (node (ref "R14") (pin "2") (pinfunction "2_2") (pintype "passive"))
    )
    (net (code "42") (name "Net-(FILTER_ATT_RIGHT-S)") (class "Default")
      (node (ref "FILTER_ATT_RIGHT") (pin "2") (pinfunction "S_2") (pintype "passive"))
      (node (ref "R12") (pin "2") (pinfunction "2_2") (pintype "passive"))
    )
    (net (code "43") (name "Net-(FILTER_LEFT-E)") (class "Default")
      (node (ref "FILTER_LEFT") (pin "3") (pinfunction "E_3") (pintype "passive"))
      (node (ref "R37") (pin "1") (pinfunction "1_1") (pintype "passive"))
    )
    (net (code "44") (name "Net-(FILTER_LEFT-S)") (class "Default")
      (node (ref "FILTER_LEFT") (pin "2") (pinfunction "S_2") (pintype "passive"))
      (node (ref "R32") (pin "2") (pinfunction "2_2") (pintype "passive"))
    )
    (net (code "45") (name "Net-(FILTER_LEFT_CV-2)") (class "Default")
      (node (ref "FILTER_LEFT_CV") (pin "P$1") (pinfunction "2_P$1") (pintype "passive"))
      (node (ref "R33") (pin "1") (pinfunction "1_1") (pintype "passive"))
    )
    (net (code "46") (name "Net-(FILTER_RIGHT-E)") (class "Default")
      (node (ref "FILTER_RIGHT") (pin "3") (pinfunction "E_3") (pintype "passive"))
      (node (ref "R26") (pin "1") (pinfunction "1_1") (pintype "passive"))
    )
    (net (code "47") (name "Net-(FILTER_RIGHT-S)") (class "Default")
      (node (ref "FILTER_RIGHT") (pin "2") (pinfunction "S_2") (pintype "passive"))
      (node (ref "R10") (pin "2") (pinfunction "2_2") (pintype "passive"))
    )
    (net (code "48") (name "Net-(FILTER_RIGHT_CV-2)") (class "Default")
      (node (ref "FILTER_RIGHT_CV") (pin "P$1") (pinfunction "2_P$1") (pintype "passive"))
      (node (ref "R12") (pin "1") (pinfunction "1_1") (pintype "passive"))
    )
    (net (code "49") (name "Net-(IC1A--IN)") (class "Default")
      (node (ref "IC1") (pin "2") (pinfunction "-IN_2") (pintype "input"))
      (node (ref "R11") (pin "2") (pinfunction "2_2") (pintype "passive"))
      (node (ref "R16") (pin "1") (pinfunction "1_1") (pintype "passive"))
      (node (ref "R9") (pin "1") (pinfunction "1_1") (pintype "passive"))
    )
    (net (code "50") (name "Net-(IC1A-OUT)") (class "Default")
      (node (ref "IC1") (pin "1") (pinfunction "OUT_1") (pintype "output"))
      (node (ref "R11") (pin "1") (pinfunction "1_1") (pintype "passive"))
      (node (ref "R13") (pin "2") (pinfunction "2_2") (pintype "passive"))
    )
    (net (code "51") (name "Net-(IC1B--IN)") (class "Default")
      (node (ref "IC1") (pin "6") (pinfunction "-IN_6") (pintype "input"))
      (node (ref "R1") (pin "2") (pinfunction "2_2") (pintype "passive"))
      (node (ref "R3") (pin "1") (pinfunction "1_1") (pintype "passive"))
    )
    (net (code "52") (name "Net-(IC2A-+IN)") (class "Default")
      (node (ref "C25") (pin "-") (pinfunction "-_-") (pintype "passive"))
      (node (ref "IC2") (pin "3") (pinfunction "+IN_3") (pintype "input"))
    )
    (net (code "53") (name "Net-(IC2A--IN)") (class "Default")
      (node (ref "IC2") (pin "1") (pinfunction "OUT_1") (pintype "output"))
      (node (ref "IC2") (pin "2") (pinfunction "-IN_2") (pintype "input"))
      (node (ref "R42") (pin "2") (pinfunction "2_2") (pintype "passive"))
    )
    (net (code "54") (name "Net-(IC2B-+IN)") (class "Default")
      (node (ref "C4") (pin "-") (pinfunction "-_-") (pintype "passive"))
      (node (ref "IC2") (pin "5") (pinfunction "+IN_5") (pintype "input"))
    )
    (net (code "55") (name "Net-(IC2B--IN)") (class "Default")
      (node (ref "IC2") (pin "6") (pinfunction "-IN_6") (pintype "input"))
      (node (ref "IC2") (pin "7") (pinfunction "OUT_7") (pintype "output"))
      (node (ref "R4") (pin "2") (pinfunction "2_2") (pintype "passive"))
    )
    (net (code "56") (name "Net-(IC3A--IN)") (class "Default")
      (node (ref "C11") (pin "1") (pinfunction "1_1") (pintype "passive"))
      (node (ref "IC3") (pin "2") (pinfunction "-IN_2") (pintype "input"))
      (node (ref "R25") (pin "1") (pinfunction "1_1") (pintype "passive"))
      (node (ref "R29") (pin "2") (pinfunction "2_2") (pintype "passive"))
      (node (ref "R30") (pin "2") (pinfunction "2_2") (pintype "passive"))
    )
    (net (code "57") (name "Net-(IC3A-OUT)") (class "Default")
      (node (ref "C11") (pin "2") (pinfunction "2_2") (pintype "passive"))
      (node (ref "IC3") (pin "1") (pinfunction "OUT_1") (pintype "output"))
      (node (ref "R25") (pin "2") (pinfunction "2_2") (pintype "passive"))
      (node (ref "R44") (pin "2") (pinfunction "2_2") (pintype "passive"))
    )
    (net (code "58") (name "Net-(IC3B--IN)") (class "Default")
      (node (ref "C24") (pin "1") (pinfunction "1_1") (pintype "passive"))
      (node (ref "IC3") (pin "6") (pinfunction "-IN_6") (pintype "input"))
      (node (ref "R31") (pin "2") (pinfunction "2_2") (pintype "passive"))
      (node (ref "R39") (pin "1") (pinfunction "1_1") (pintype "passive"))
      (node (ref "R53") (pin "2") (pinfunction "2_2") (pintype "passive"))
    )
    (net (code "59") (name "Net-(IC3B-OUT)") (class "Default")
      (node (ref "C24") (pin "2") (pinfunction "2_2") (pintype "passive"))
      (node (ref "IC3") (pin "7") (pinfunction "OUT_7") (pintype "output"))
      (node (ref "R39") (pin "2") (pinfunction "2_2") (pintype "passive"))
      (node (ref "R41") (pin "2") (pinfunction "2_2") (pintype "passive"))
    )
    (net (code "60") (name "Net-(IC3C--IN)") (class "Default")
      (node (ref "C16") (pin "1") (pinfunction "1_1") (pintype "passive"))
      (node (ref "IC3") (pin "9") (pinfunction "-IN_9") (pintype "input"))
      (node (ref "R17") (pin "2") (pinfunction "2_2") (pintype "passive"))
      (node (ref "R18") (pin "2") (pinfunction "2_2") (pintype "passive"))
      (node (ref "R19") (pin "1") (pinfunction "1_1") (pintype "passive"))
    )
    (net (code "61") (name "Net-(IC3C-OUT)") (class "Default")
      (node (ref "C16") (pin "2") (pinfunction "2_2") (pintype "passive"))
      (node (ref "IC3") (pin "8") (pinfunction "OUT_8") (pintype "output"))
      (node (ref "R19") (pin "2") (pinfunction "2_2") (pintype "passive"))
      (node (ref "R43") (pin "2") (pinfunction "2_2") (pintype "passive"))
    )
    (net (code "62") (name "Net-(IC3D--IN)") (class "Default")
      (node (ref "C23") (pin "1") (pinfunction "1_1") (pintype "passive"))
      (node (ref "IC3") (pin "13") (pinfunction "-IN_13") (pintype "input"))
      (node (ref "R20") (pin "2") (pinfunction "2_2") (pintype "passive"))
      (node (ref "R23") (pin "2") (pinfunction "2_2") (pintype "passive"))
      (node (ref "R27") (pin "1") (pinfunction "1_1") (pintype "passive"))
    )
    (net (code "63") (name "Net-(IC3D-OUT)") (class "Default")
      (node (ref "C23") (pin "2") (pinfunction "2_2") (pintype "passive"))
      (node (ref "IC3") (pin "14") (pinfunction "OUT_14") (pintype "output"))
      (node (ref "R27") (pin "2") (pinfunction "2_2") (pintype "passive"))
      (node (ref "R40") (pin "2") (pinfunction "2_2") (pintype "passive"))
    )
    (net (code "64") (name "Net-(IC5A--IN)") (class "Default")
      (node (ref "C6") (pin "1") (pinfunction "1_1") (pintype "passive"))
      (node (ref "IC5") (pin "2") (pinfunction "-IN_2") (pintype "input"))
      (node (ref "R2") (pin "1") (pinfunction "1_1") (pintype "passive"))
      (node (ref "R6") (pin "2") (pinfunction "2_2") (pintype "passive"))
    )
    (net (code "65") (name "Net-(IC5A-OUT)") (class "Default")
      (node (ref "C6") (pin "2") (pinfunction "2_2") (pintype "passive"))
      (node (ref "IC5") (pin "1") (pinfunction "OUT_1") (pintype "output"))
      (node (ref "R6") (pin "1") (pinfunction "1_1") (pintype "passive"))
      (node (ref "R8") (pin "2") (pinfunction "2_2") (pintype "passive"))
    )
    (net (code "66") (name "Net-(IC5B--IN)") (class "Default")
      (node (ref "C27") (pin "1") (pinfunction "1_1") (pintype "passive"))
      (node (ref "IC5") (pin "6") (pinfunction "-IN_6") (pintype "input"))
      (node (ref "R47") (pin "1") (pinfunction "1_1") (pintype "passive"))
      (node (ref "R48") (pin "2") (pinfunction "2_2") (pintype "passive"))
    )
    (net (code "67") (name "Net-(IC5B-OUT)") (class "Default")
      (node (ref "C27") (pin "2") (pinfunction "2_2") (pintype "passive"))
      (node (ref "IC5") (pin "7") (pinfunction "OUT_7") (pintype "output"))
      (node (ref "R48") (pin "1") (pinfunction "1_1") (pintype "passive"))
      (node (ref "R49") (pin "2") (pinfunction "2_2") (pintype "passive"))
    )
    (net (code "68") (name "Net-(IC6-(PCINT14{slash}MISO)PB6)") (class "Default")
      (node (ref "IC6") (pin "2") (pinfunction "(PCINT14/MISO)PB6_2") (pintype "bidirectional"))
      (node (ref "PGM") (pin "1") (pinfunction "1_1") (pintype "passive"))
    )
    (net (code "69") (name "Net-(IC6-(PCINT15{slash}SCK)PB7)") (class "Default")
      (node (ref "IC6") (pin "3") (pinfunction "(PCINT15/SCK)PB7_3") (pintype "bidirectional"))
      (node (ref "PGM") (pin "3") (pinfunction "3_3") (pintype "passive"))
    )
    (net (code "70") (name "Net-(IC6-(PCINT16{slash}SCL)PC0)") (class "Default")
      (node (ref "IC6") (pin "19") (pinfunction "(PCINT16/SCL)PC0_19") (pintype "output"))
      (node (ref "U$1") (pin "10") (pinfunction "CE_10") (pintype "input"))
    )
    (net (code "71") (name "Net-(IC6-(PCINT17{slash}SDA)PC1)") (class "Default")
      (node (ref "IC6") (pin "20") (pinfunction "(PCINT17/SDA)PC1_20") (pintype "output"))
      (node (ref "U$1") (pin "9") (pinfunction "R/W_9") (pintype "input"))
    )
    (net (code "72") (name "Net-(IC6-(PCINT18{slash}TCK)PC2)") (class "Default")
      (node (ref "IC6") (pin "21") (pinfunction "(PCINT18/TCK)PC2_21") (pintype "output"))
      (node (ref "U$1") (pin "19") (pinfunction "RES_19") (pintype "input"))
    )
    (net (code "73") (name "Net-(IC6-(PCINT19{slash}TMS)PC3)") (class "Default")
      (node (ref "IC6") (pin "22") (pinfunction "(PCINT19/TMS)PC3_22") (pintype "output"))
      (node (ref "U$1") (pin "13") (pinfunction "FCQ_13") (pintype "bidirectional"))
    )
    (net (code "74") (name "Net-(IC6-(PCINT20{slash}TDO)PC4)") (class "Default")
      (node (ref "IC6") (pin "23") (pinfunction "(PCINT20/TDO)PC4_23") (pintype "output"))
      (node (ref "U$1") (pin "12") (pinfunction "FA_12") (pintype "bidirectional"))
    )
    (net (code "75") (name "Net-(IC6-(PCINT21{slash}TDI)PC5)") (class "Default")
      (node (ref "IC6") (pin "24") (pinfunction "(PCINT21/TDI)PC5_24") (pintype "output"))
      (node (ref "U$1") (pin "11") (pinfunction "CHS_11") (pintype "bidirectional"))
    )
    (net (code "76") (name "Net-(IC7A-OUT)") (class "Default")
      (node (ref "IC7") (pin "1") (pinfunction "OUT_1") (pintype "output"))
      (node (ref "R14") (pin "1") (pinfunction "1_1") (pintype "passive"))
      (node (ref "R22") (pin "2") (pinfunction "2_2") (pintype "passive"))
    )
    (net (code "77") (name "Net-(IC8A-OUT)") (class "Default")
      (node (ref "IC8") (pin "1") (pinfunction "OUT_1") (pintype "output"))
      (node (ref "R34") (pin "1") (pinfunction "1_1") (pintype "passive"))
      (node (ref "R36") (pin "2") (pinfunction "2_2") (pintype "passive"))
    )
    (net (code "78") (name "Net-(IC8B-OUT)") (class "Default")
      (node (ref "C9") (pin "2") (pinfunction "2_2") (pintype "passive"))
      (node (ref "IC8") (pin "7") (pinfunction "OUT_7") (pintype "output"))
      (node (ref "R28") (pin "2") (pinfunction "2_2") (pintype "passive"))
      (node (ref "R35") (pin "1") (pinfunction "1_1") (pintype "passive"))
    )
    (net (code "79") (name "Net-(MIX_OUT-2)") (class "Default")
      (node (ref "MIX_OUT") (pin "P$1") (pinfunction "2_P$1") (pintype "passive"))
      (node (ref "R13") (pin "1") (pinfunction "1_1") (pintype "passive"))
    )
    (net (code "80") (name "Net-(RES_1_ATTN-E)") (class "Default")
      (node (ref "RES_1_ATTN") (pin "3") (pinfunction "E_3") (pintype "passive"))
      (node (ref "RES_1_CV") (pin "P$1") (pinfunction "2_P$1") (pintype "passive"))
    )
    (net (code "81") (name "Net-(RES_1_ATTN-S)") (class "Default")
      (node (ref "R29") (pin "1") (pinfunction "1_1") (pintype "passive"))
      (node (ref "RES_1_ATTN") (pin "2") (pinfunction "S_2") (pintype "passive"))
    )
    (net (code "82") (name "Net-(RES_1_OFF-S)") (class "Default")
      (node (ref "R30") (pin "1") (pinfunction "1_1") (pintype "passive"))
      (node (ref "RES_1_OFF") (pin "2") (pinfunction "S_2") (pintype "passive"))
    )
    (net (code "83") (name "Net-(RES_2_ATTN-E)") (class "Default")
      (node (ref "RES_2_ATTN") (pin "3") (pinfunction "E_3") (pintype "passive"))
      (node (ref "RES_2_CV") (pin "P$1") (pinfunction "2_P$1") (pintype "passive"))
    )
    (net (code "84") (name "Net-(RES_2_ATTN-S)") (class "Default")
      (node (ref "R17") (pin "1") (pinfunction "1_1") (pintype "passive"))
      (node (ref "RES_2_ATTN") (pin "2") (pinfunction "S_2") (pintype "passive"))
    )
    (net (code "85") (name "Net-(RES_2_OFF-S)") (class "Default")
      (node (ref "R18") (pin "1") (pinfunction "1_1") (pintype "passive"))
      (node (ref "RES_2_OFF") (pin "2") (pinfunction "S_2") (pintype "passive"))
    )
    (net (code "86") (name "Net-(U$1-OSC)") (class "Default")
      (node (ref "U$1") (pin "18") (pinfunction "OSC_18") (pintype "input"))
      (node (ref "U1") (pin "4") (pinfunction "2Y_4") (pintype "output"))
    )
    (net (code "87") (name "Net-(U1-1A)") (class "Default")
      (node (ref "QF1") (pin "3") (pinfunction "3_3") (pintype "passive"))
      (node (ref "R38") (pin "2") (pinfunction "2_2") (pintype "passive"))
      (node (ref "U1") (pin "1") (pinfunction "1A_1") (pintype "input"))
    )
    (net (code "88") (name "Net-(U1-1Y)") (class "Default")
      (node (ref "QF1") (pin "1") (pinfunction "1_1") (pintype "passive"))
      (node (ref "R38") (pin "1") (pinfunction "1_1") (pintype "passive"))
      (node (ref "U1") (pin "3") (pinfunction "2A_3") (pintype "input"))
      (node (ref "U1") (pin "6") (pinfunction "1Y_6") (pintype "output"))
    )
    (net (code "89") (name "RESET") (class "Default")
      (node (ref "IC6") (pin "4") (pinfunction "RESET_4") (pintype "input"))
      (node (ref "PGM") (pin "5") (pinfunction "5_5") (pintype "passive"))
      (node (ref "R21") (pin "1") (pinfunction "1_1") (pintype "passive"))
    )
    (net (code "90") (name "TX") (class "Default")
      (node (ref "IC6") (pin "10") (pinfunction "(PCINT25/TXD0)PD1_10") (pintype "bidirectional"))
      (node (ref "TX") (pin "2") (pinfunction "2_2") (pintype "passive"))
    )
    (net (code "91") (name "XTAL1") (class "Default")
      (node (ref "C19") (pin "2") (pinfunction "2_2") (pintype "passive"))
      (node (ref "IC6") (pin "8") (pinfunction "XTAL1_8") (pintype "bidirectional"))
      (node (ref "Y2") (pin "2") (pinfunction "2_2") (pintype "passive"))
    )
    (net (code "92") (name "XTAL2") (class "Default")
      (node (ref "C20") (pin "2") (pinfunction "2_2") (pintype "passive"))
      (node (ref "IC6") (pin "7") (pinfunction "XTAL2_7") (pintype "bidirectional"))
      (node (ref "Y2") (pin "1") (pinfunction "1_1") (pintype "passive"))
    )
    (net (code "93") (name "unconnected-(A_IN_1-3-PadP$2)") (class "Default")
      (node (ref "A_IN_1") (pin "P$2") (pinfunction "3_P$2") (pintype "passive"))
    )
    (net (code "94") (name "unconnected-(A_IN_2-3-PadP$2)") (class "Default")
      (node (ref "A_IN_2") (pin "P$2") (pinfunction "3_P$2") (pintype "passive"))
    )
    (net (code "95") (name "unconnected-(A_OUT_1-3-PadP$2)") (class "Default")
      (node (ref "A_OUT_1") (pin "P$2") (pinfunction "3_P$2") (pintype "passive"))
    )
    (net (code "96") (name "unconnected-(A_OUT_2-3-PadP$2)") (class "Default")
      (node (ref "A_OUT_2") (pin "P$2") (pinfunction "3_P$2") (pintype "passive"))
    )
    (net (code "97") (name "unconnected-(FILTER_LEFT_CV-3-PadP$2)") (class "Default")
      (node (ref "FILTER_LEFT_CV") (pin "P$2") (pinfunction "3_P$2") (pintype "passive"))
    )
    (net (code "98") (name "unconnected-(FILTER_RIGHT_CV-3-PadP$2)") (class "Default")
      (node (ref "FILTER_RIGHT_CV") (pin "P$2") (pinfunction "3_P$2") (pintype "passive"))
    )
    (net (code "99") (name "unconnected-(IC6-(PCINT6{slash}ADC6)PA6-Pad31)") (class "Default")
      (node (ref "IC6") (pin "31") (pinfunction "(PCINT6/ADC6)PA6_31") (pintype "bidirectional"))
    )
    (net (code "100") (name "unconnected-(IC6-(PCINT7{slash}ADC7)PA7-Pad30)") (class "Default")
      (node (ref "IC6") (pin "30") (pinfunction "(PCINT7/ADC7)PA7_30") (pintype "bidirectional"))
    )
    (net (code "101") (name "unconnected-(IC6-(PCINT12{slash}OC0B{slash}~{SS})PB4-Pad44)") (class "Default")
      (node (ref "IC6") (pin "44") (pinfunction "(PCINT12/OC0B/~{SS})PB4_44") (pintype "bidirectional"))
    )
    (net (code "102") (name "unconnected-(IC6-(PCINT22{slash}TOSC1)PC6-Pad25)") (class "Default")
      (node (ref "IC6") (pin "25") (pinfunction "(PCINT22/TOSC1)PC6_25") (pintype "output"))
    )
    (net (code "103") (name "unconnected-(IC6-(PCINT23{slash}TOSC2)PC7-Pad26)") (class "Default")
      (node (ref "IC6") (pin "26") (pinfunction "(PCINT23/TOSC2)PC7_26") (pintype "output"))
    )
    (net (code "104") (name "unconnected-(IC6-(PCINT24{slash}RXD0)PD0-Pad9)") (class "Default")
      (node (ref "IC6") (pin "9") (pinfunction "(PCINT24/RXD0)PD0_9") (pintype "bidirectional"))
    )
    (net (code "105") (name "unconnected-(IC6-(PCINT30{slash}OC2B{slash}ICP)PD6-Pad15)") (class "Default")
      (node (ref "IC6") (pin "15") (pinfunction "(PCINT30/OC2B/ICP)PD6_15") (pintype "bidirectional"))
    )
    (net (code "106") (name "unconnected-(IC6-(PCINT31{slash}OC2A)PD7-Pad16)") (class "Default")
      (node (ref "IC6") (pin "16") (pinfunction "(PCINT31/OC2A)PD7_16") (pintype "bidirectional"))
    )
    (net (code "107") (name "unconnected-(MIX_OUT-3-PadP$2)") (class "Default")
      (node (ref "MIX_OUT") (pin "P$2") (pinfunction "3_P$2") (pintype "passive"))
    )
    (net (code "108") (name "unconnected-(RES_1_CV-3-PadP$2)") (class "Default")
      (node (ref "RES_1_CV") (pin "P$2") (pinfunction "3_P$2") (pintype "passive"))
    )
    (net (code "109") (name "unconnected-(RES_2_CV-3-PadP$2)") (class "Default")
      (node (ref "RES_2_CV") (pin "P$2") (pinfunction "3_P$2") (pintype "passive"))
    )
    (net (code "110") (name "unconnected-(U$1-NC1-Pad15)") (class "Default")
      (node (ref "U$1") (pin "15") (pinfunction "NC1_15") (pintype "input"))
    )
    (net (code "111") (name "unconnected-(U$1-NC2-Pad16)") (class "Default")
      (node (ref "U$1") (pin "16") (pinfunction "NC2_16") (pintype "input"))
    )
    (net (code "112") (name "unconnected-(U$1-NC3-Pad17)") (class "Default")
      (node (ref "U$1") (pin "17") (pinfunction "NC3_17") (pintype "input"))
    )
  )
)
